# breakout.net
KiCad netlist of a schematic drawn in EAGLE
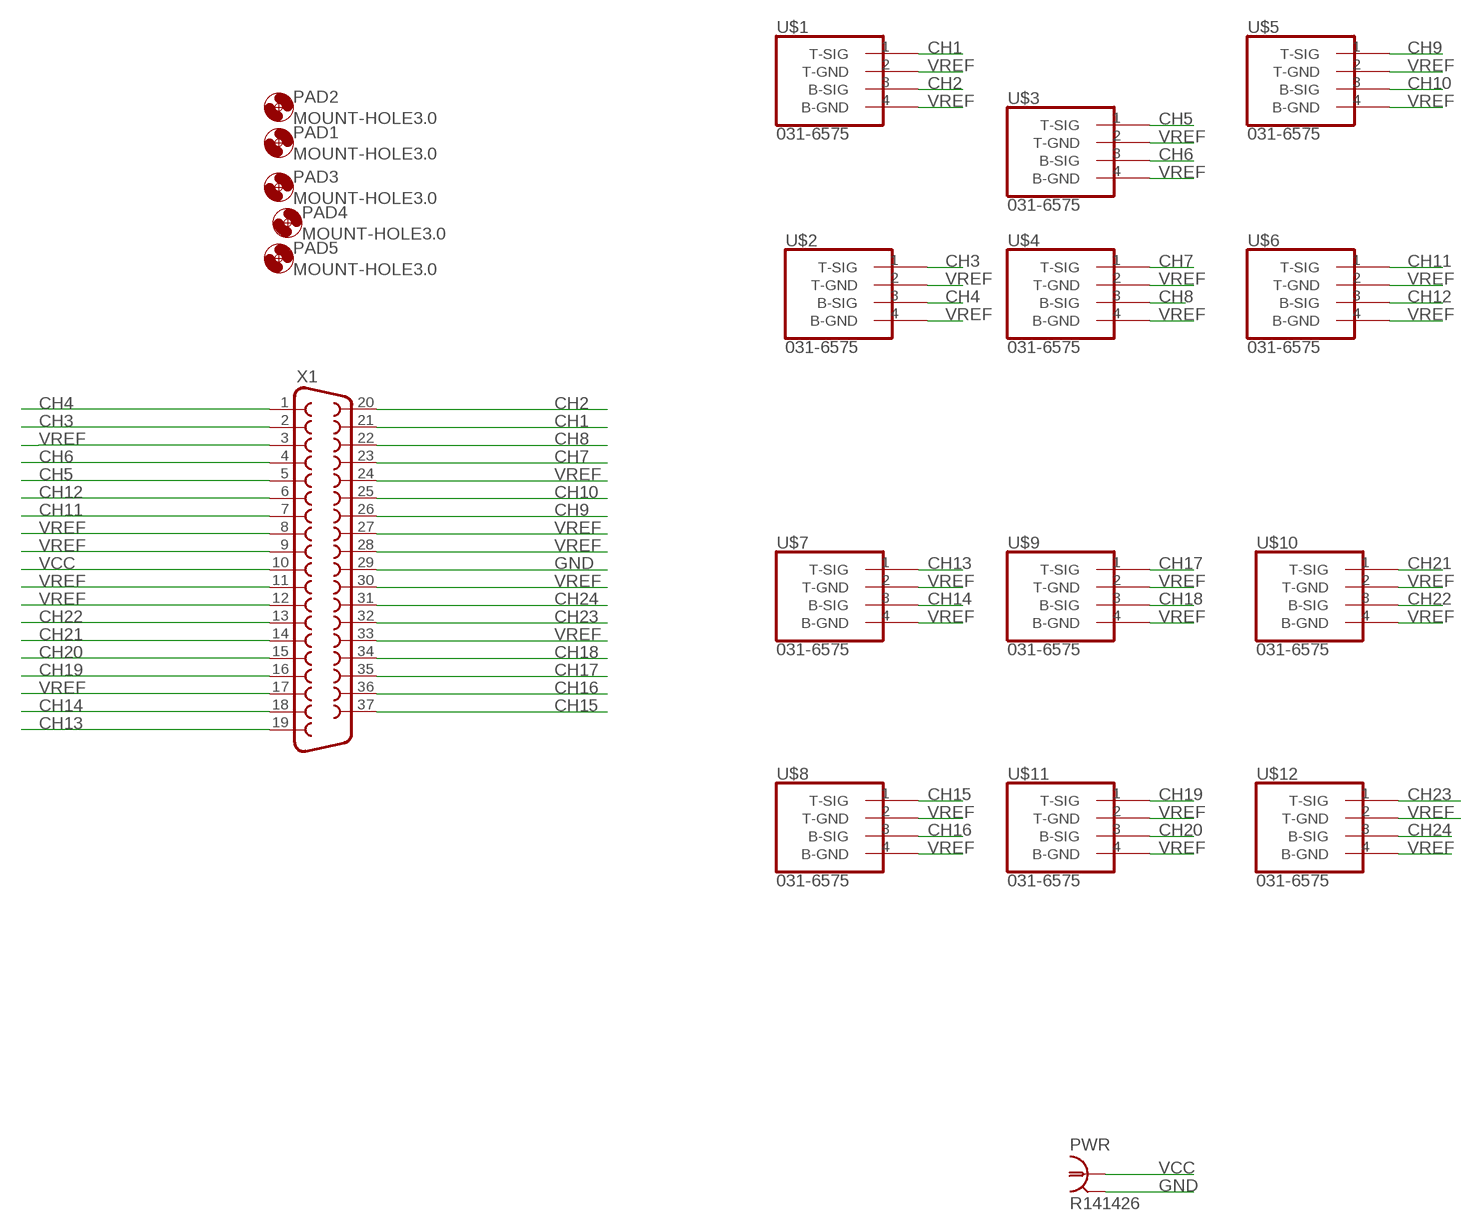
[diagram p0: schematic, sheet 1]

(export (version "E")
  (design (tool "Eeschema 10.0.6"))
  (components
    (comp (ref "PAD1")
      (value "MOUNT-HOLE3.0")
      (footprint "eagle-import:3,0")
      (libsource (lib "eagle-import") (part "MOUNT-HOLE3.0"))
    )
    (comp (ref "PAD2")
      (value "MOUNT-HOLE3.0")
      (footprint "eagle-import:3,0")
      (libsource (lib "eagle-import") (part "MOUNT-HOLE3.0"))
    )
    (comp (ref "PAD3")
      (value "MOUNT-HOLE3.0")
      (footprint "eagle-import:3,0")
      (libsource (lib "eagle-import") (part "MOUNT-HOLE3.0"))
    )
    (comp (ref "PAD4")
      (value "MOUNT-HOLE3.0")
      (footprint "eagle-import:3,0")
      (libsource (lib "eagle-import") (part "MOUNT-HOLE3.0"))
    )
    (comp (ref "PAD5")
      (value "MOUNT-HOLE3.0")
      (footprint "eagle-import:3,0")
      (libsource (lib "eagle-import") (part "MOUNT-HOLE3.0"))
    )
    (comp (ref "PWR")
      (value "R141426")
      (footprint "eagle-import:R141426")
      (fields (field (name "MF") "FARNELL") (field (name "MPN") "R141426161"))
      (libsource (lib "eagle-import") (part "R141426"))
    )
    (comp (ref "U$1")
      (value "031-6575")
      (footprint "eagle-import:031-6575")
      (libsource (lib "eagle-import") (part "031-6575"))
    )
    (comp (ref "U$2")
      (value "031-6575")
      (footprint "eagle-import:031-6575")
      (libsource (lib "eagle-import") (part "031-6575"))
    )
    (comp (ref "U$3")
      (value "031-6575")
      (footprint "eagle-import:031-6575")
      (libsource (lib "eagle-import") (part "031-6575"))
    )
    (comp (ref "U$4")
      (value "031-6575")
      (footprint "eagle-import:031-6575")
      (libsource (lib "eagle-import") (part "031-6575"))
    )
    (comp (ref "U$5")
      (value "031-6575")
      (footprint "eagle-import:031-6575")
      (libsource (lib "eagle-import") (part "031-6575"))
    )
    (comp (ref "U$6")
      (value "031-6575")
      (footprint "eagle-import:031-6575")
      (libsource (lib "eagle-import") (part "031-6575"))
    )
    (comp (ref "U$7")
      (value "031-6575")
      (footprint "eagle-import:031-6575")
      (libsource (lib "eagle-import") (part "031-6575"))
    )
    (comp (ref "U$8")
      (value "031-6575")
      (footprint "eagle-import:031-6575")
      (libsource (lib "eagle-import") (part "031-6575"))
    )
    (comp (ref "U$9")
      (value "031-6575")
      (footprint "eagle-import:031-6575")
      (libsource (lib "eagle-import") (part "031-6575"))
    )
    (comp (ref "U$10")
      (value "031-6575")
      (footprint "eagle-import:031-6575")
      (libsource (lib "eagle-import") (part "031-6575"))
    )
    (comp (ref "U$11")
      (value "031-6575")
      (footprint "eagle-import:031-6575")
      (libsource (lib "eagle-import") (part "031-6575"))
    )
    (comp (ref "U$12")
      (value "031-6575")
      (footprint "eagle-import:031-6575")
      (libsource (lib "eagle-import") (part "031-6575"))
    )
    (comp (ref "X1")
      (value "F37HP")
      (footprint "eagle-import:F37HP")
      (libsource (lib "eagle-import") (part "F37HP"))
    )
  )
  (nets
    (net (code "1") (name "/CH1") (class "Default")
      (node (ref "U$1") (pin "1") (pinfunction "T-SIG_1") (pintype "bidirectional"))
      (node (ref "X1") (pin "21") (pinfunction "21_21") (pintype "passive"))
    )
    (net (code "2") (name "/CH2") (class "Default")
      (node (ref "U$1") (pin "3") (pinfunction "B-SIG_3") (pintype "bidirectional"))
      (node (ref "X1") (pin "20") (pinfunction "20_20") (pintype "passive"))
    )
    (net (code "3") (name "/CH3") (class "Default")
      (node (ref "U$2") (pin "1") (pinfunction "T-SIG_1") (pintype "bidirectional"))
      (node (ref "X1") (pin "2") (pinfunction "2_2") (pintype "passive"))
    )
    (net (code "4") (name "/CH4") (class "Default")
      (node (ref "U$2") (pin "3") (pinfunction "B-SIG_3") (pintype "bidirectional"))
      (node (ref "X1") (pin "1") (pinfunction "1_1") (pintype "passive"))
    )
    (net (code "5") (name "/CH5") (class "Default")
      (node (ref "U$3") (pin "1") (pinfunction "T-SIG_1") (pintype "bidirectional"))
      (node (ref "X1") (pin "5") (pinfunction "5_5") (pintype "passive"))
    )
    (net (code "6") (name "/CH6") (class "Default")
      (node (ref "U$3") (pin "3") (pinfunction "B-SIG_3") (pintype "bidirectional"))
      (node (ref "X1") (pin "4") (pinfunction "4_4") (pintype "passive"))
    )
    (net (code "7") (name "/CH7") (class "Default")
      (node (ref "U$4") (pin "1") (pinfunction "T-SIG_1") (pintype "bidirectional"))
      (node (ref "X1") (pin "23") (pinfunction "23_23") (pintype "passive"))
    )
    (net (code "8") (name "/CH8") (class "Default")
      (node (ref "U$4") (pin "3") (pinfunction "B-SIG_3") (pintype "bidirectional"))
      (node (ref "X1") (pin "22") (pinfunction "22_22") (pintype "passive"))
    )
    (net (code "9") (name "/CH9") (class "Default")
      (node (ref "U$5") (pin "1") (pinfunction "T-SIG_1") (pintype "bidirectional"))
      (node (ref "X1") (pin "26") (pinfunction "26_26") (pintype "passive"))
    )
    (net (code "10") (name "/CH10") (class "Default")
      (node (ref "U$5") (pin "3") (pinfunction "B-SIG_3") (pintype "bidirectional"))
      (node (ref "X1") (pin "25") (pinfunction "25_25") (pintype "passive"))
    )
    (net (code "11") (name "/CH11") (class "Default")
      (node (ref "U$6") (pin "1") (pinfunction "T-SIG_1") (pintype "bidirectional"))
      (node (ref "X1") (pin "7") (pinfunction "7_7") (pintype "passive"))
    )
    (net (code "12") (name "/CH12") (class "Default")
      (node (ref "U$6") (pin "3") (pinfunction "B-SIG_3") (pintype "bidirectional"))
      (node (ref "X1") (pin "6") (pinfunction "6_6") (pintype "passive"))
    )
    (net (code "13") (name "/CH13") (class "Default")
      (node (ref "U$7") (pin "1") (pinfunction "T-SIG_1") (pintype "bidirectional"))
      (node (ref "X1") (pin "19") (pinfunction "19_19") (pintype "passive"))
    )
    (net (code "14") (name "/CH14") (class "Default")
      (node (ref "U$7") (pin "3") (pinfunction "B-SIG_3") (pintype "bidirectional"))
      (node (ref "X1") (pin "18") (pinfunction "18_18") (pintype "passive"))
    )
    (net (code "15") (name "/CH15") (class "Default")
      (node (ref "U$8") (pin "1") (pinfunction "T-SIG_1") (pintype "bidirectional"))
      (node (ref "X1") (pin "37") (pinfunction "37_37") (pintype "passive"))
    )
    (net (code "16") (name "/CH16") (class "Default")
      (node (ref "U$8") (pin "3") (pinfunction "B-SIG_3") (pintype "bidirectional"))
      (node (ref "X1") (pin "36") (pinfunction "36_36") (pintype "passive"))
    )
    (net (code "17") (name "/CH17") (class "Default")
      (node (ref "U$9") (pin "1") (pinfunction "T-SIG_1") (pintype "bidirectional"))
      (node (ref "X1") (pin "35") (pinfunction "35_35") (pintype "passive"))
    )
    (net (code "18") (name "/CH18") (class "Default")
      (node (ref "U$9") (pin "3") (pinfunction "B-SIG_3") (pintype "bidirectional"))
      (node (ref "X1") (pin "34") (pinfunction "34_34") (pintype "passive"))
    )
    (net (code "19") (name "/CH19") (class "Default")
      (node (ref "U$11") (pin "1") (pinfunction "T-SIG_1") (pintype "bidirectional"))
      (node (ref "X1") (pin "16") (pinfunction "16_16") (pintype "passive"))
    )
    (net (code "20") (name "/CH20") (class "Default")
      (node (ref "U$11") (pin "3") (pinfunction "B-SIG_3") (pintype "bidirectional"))
      (node (ref "X1") (pin "15") (pinfunction "15_15") (pintype "passive"))
    )
    (net (code "21") (name "/CH21") (class "Default")
      (node (ref "U$10") (pin "1") (pinfunction "T-SIG_1") (pintype "bidirectional"))
      (node (ref "X1") (pin "14") (pinfunction "14_14") (pintype "passive"))
    )
    (net (code "22") (name "/CH22") (class "Default")
      (node (ref "U$10") (pin "3") (pinfunction "B-SIG_3") (pintype "bidirectional"))
      (node (ref "X1") (pin "13") (pinfunction "13_13") (pintype "passive"))
    )
    (net (code "23") (name "/CH23") (class "Default")
      (node (ref "U$12") (pin "1") (pinfunction "T-SIG_1") (pintype "bidirectional"))
      (node (ref "X1") (pin "32") (pinfunction "32_32") (pintype "passive"))
    )
    (net (code "24") (name "/CH24") (class "Default")
      (node (ref "U$12") (pin "3") (pinfunction "B-SIG_3") (pintype "bidirectional"))
      (node (ref "X1") (pin "31") (pinfunction "31_31") (pintype "passive"))
    )
    (net (code "25") (name "/GND") (class "Default")
      (node (ref "PWR") (pin "2") (pinfunction "2_2") (pintype "passive"))
      (node (ref "PWR") (pin "3") (pinfunction "2_3") (pintype "passive"))
      (node (ref "PWR") (pin "4") (pinfunction "2_4") (pintype "passive"))
      (node (ref "PWR") (pin "5") (pinfunction "2_5") (pintype "passive"))
      (node (ref "X1") (pin "29") (pinfunction "29_29") (pintype "passive"))
    )
    (net (code "26") (name "/VCC") (class "Default")
      (node (ref "PWR") (pin "1") (pinfunction "1_1") (pintype "passive"))
      (node (ref "X1") (pin "10") (pinfunction "10_10") (pintype "passive"))
    )
    (net (code "27") (name "/VREF") (class "Default")
      (node (ref "U$1") (pin "2") (pinfunction "T-GND_2") (pintype "bidirectional"))
      (node (ref "U$1") (pin "4") (pinfunction "B-GND_4") (pintype "bidirectional"))
      (node (ref "U$10") (pin "2") (pinfunction "T-GND_2") (pintype "bidirectional"))
      (node (ref "U$10") (pin "4") (pinfunction "B-GND_4") (pintype "bidirectional"))
      (node (ref "U$11") (pin "2") (pinfunction "T-GND_2") (pintype "bidirectional"))
      (node (ref "U$11") (pin "4") (pinfunction "B-GND_4") (pintype "bidirectional"))
      (node (ref "U$12") (pin "2") (pinfunction "T-GND_2") (pintype "bidirectional"))
      (node (ref "U$12") (pin "4") (pinfunction "B-GND_4") (pintype "bidirectional"))
      (node (ref "U$2") (pin "2") (pinfunction "T-GND_2") (pintype "bidirectional"))
      (node (ref "U$2") (pin "4") (pinfunction "B-GND_4") (pintype "bidirectional"))
      (node (ref "U$3") (pin "2") (pinfunction "T-GND_2") (pintype "bidirectional"))
      (node (ref "U$3") (pin "4") (pinfunction "B-GND_4") (pintype "bidirectional"))
      (node (ref "U$4") (pin "2") (pinfunction "T-GND_2") (pintype "bidirectional"))
      (node (ref "U$4") (pin "4") (pinfunction "B-GND_4") (pintype "bidirectional"))
      (node (ref "U$5") (pin "2") (pinfunction "T-GND_2") (pintype "bidirectional"))
      (node (ref "U$5") (pin "4") (pinfunction "B-GND_4") (pintype "bidirectional"))
      (node (ref "U$6") (pin "2") (pinfunction "T-GND_2") (pintype "bidirectional"))
      (node (ref "U$6") (pin "4") (pinfunction "B-GND_4") (pintype "bidirectional"))
      (node (ref "U$7") (pin "2") (pinfunction "T-GND_2") (pintype "bidirectional"))
      (node (ref "U$7") (pin "4") (pinfunction "B-GND_4") (pintype "bidirectional"))
      (node (ref "U$8") (pin "2") (pinfunction "T-GND_2") (pintype "bidirectional"))
      (node (ref "U$8") (pin "4") (pinfunction "B-GND_4") (pintype "bidirectional"))
      (node (ref "U$9") (pin "2") (pinfunction "T-GND_2") (pintype "bidirectional"))
      (node (ref "U$9") (pin "4") (pinfunction "B-GND_4") (pintype "bidirectional"))
      (node (ref "X1") (pin "11") (pinfunction "11_11") (pintype "passive"))
      (node (ref "X1") (pin "12") (pinfunction "12_12") (pintype "passive"))
      (node (ref "X1") (pin "17") (pinfunction "17_17") (pintype "passive"))
      (node (ref "X1") (pin "24") (pinfunction "24_24") (pintype "passive"))
      (node (ref "X1") (pin "27") (pinfunction "27_27") (pintype "passive"))
      (node (ref "X1") (pin "28") (pinfunction "28_28") (pintype "passive"))
      (node (ref "X1") (pin "3") (pinfunction "3_3") (pintype "passive"))
      (node (ref "X1") (pin "30") (pinfunction "30_30") (pintype "passive"))
      (node (ref "X1") (pin "33") (pinfunction "33_33") (pintype "passive"))
      (node (ref "X1") (pin "8") (pinfunction "8_8") (pintype "passive"))
      (node (ref "X1") (pin "9") (pinfunction "9_9") (pintype "passive"))
    )
  )
)
